# Robot2.net
KiCad netlist of a schematic drawn in EAGLE
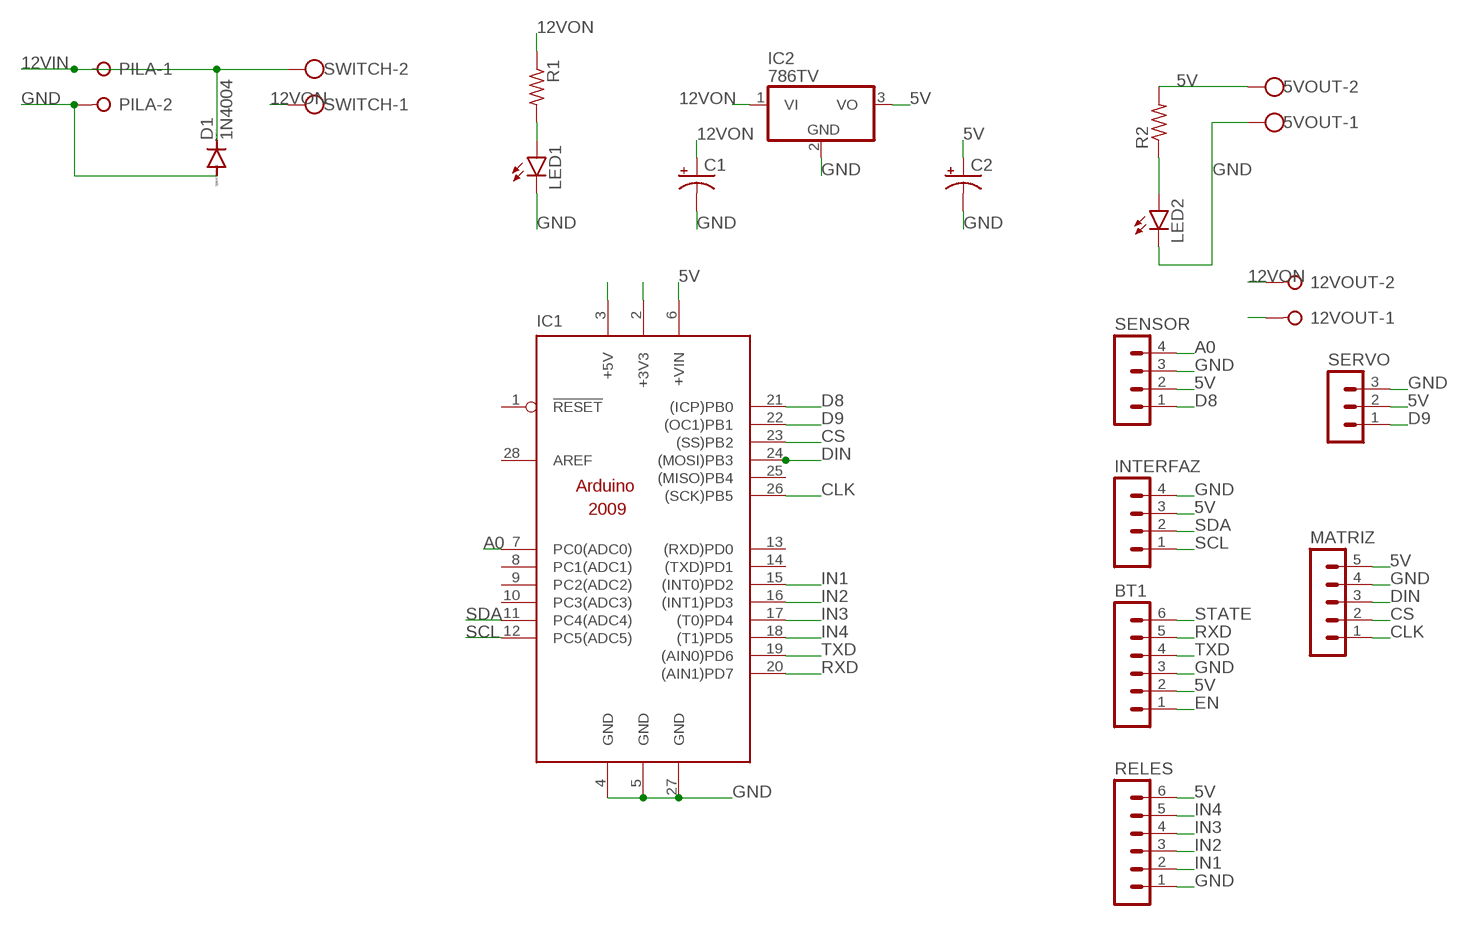
[diagram p0: schematic, sheet 1]

(export (version "E")
  (design (tool "Eeschema 10.0.6"))
  (components
    (comp (ref "5VOUT")
      (value "W237-102")
      (footprint "eagle-import:W237-102")
      (fields (field (name "MPN") "237-102"))
      (libsource (lib "eagle-import") (part "W237-102"))
    )
    (comp (ref "12VOUT")
      (value "W237-02P")
      (footprint "eagle-import:W237-132")
      (libsource (lib "eagle-import") (part "W237-02P"))
    )
    (comp (ref "BT1")
      (value "MA06-1")
      (footprint "eagle-import:MA06-1")
      (libsource (lib "eagle-import") (part "MA06-1"))
    )
    (comp (ref "C1")
      (value "CPOL-USE2,5-6E")
      (footprint "eagle-import:E2,5-6E")
      (libsource (lib "eagle-import") (part "CPOL-USE2,5-6E"))
    )
    (comp (ref "C2")
      (value "CPOL-USE2,5-6E")
      (footprint "eagle-import:E2,5-6E")
      (libsource (lib "eagle-import") (part "CPOL-USE2,5-6E"))
    )
    (comp (ref "D1")
      (value "1N4004")
      (footprint "eagle-import:DO41-10")
      (libsource (lib "eagle-import") (part "1N4004"))
    )
    (comp (ref "IC1")
      (value "ARDUINO2009_PIN_11")
      (footprint "eagle-import:ARDUINO2009_1")
      (libsource (lib "eagle-import") (part "ARDUINO2009_PIN_11"))
    )
    (comp (ref "IC2")
      (value "786TV")
      (footprint "eagle-import:TO220V")
      (libsource (lib "eagle-import") (part "78TV6"))
    )
    (comp (ref "INTERFAZ")
      (value "MA04-1")
      (footprint "eagle-import:MA04-1")
      (libsource (lib "eagle-import") (part "MA04-1"))
    )
    (comp (ref "LED1")
      (value "LED3MM")
      (footprint "eagle-import:LED3MM")
      (libsource (lib "eagle-import") (part "LED3MM"))
    )
    (comp (ref "LED2")
      (value "LED3MM")
      (footprint "eagle-import:LED3MM")
      (libsource (lib "eagle-import") (part "LED3MM"))
    )
    (comp (ref "MATRIZ")
      (value "MA05-1")
      (footprint "eagle-import:MA05-1")
      (libsource (lib "eagle-import") (part "MA05-1"))
    )
    (comp (ref "PILA")
      (value "W237-02P")
      (footprint "eagle-import:W237-132")
      (libsource (lib "eagle-import") (part "W237-02P"))
    )
    (comp (ref "R1")
      (value "R-US_0204/7")
      (footprint "eagle-import:0204_7")
      (libsource (lib "eagle-import") (part "R-US_0204/7"))
    )
    (comp (ref "R2")
      (value "R-US_0204/7")
      (footprint "eagle-import:0204_7")
      (libsource (lib "eagle-import") (part "R-US_0204/7"))
    )
    (comp (ref "RELES")
      (value "MA06-1")
      (footprint "eagle-import:MA06-1")
      (libsource (lib "eagle-import") (part "MA06-1"))
    )
    (comp (ref "SENSOR")
      (value "MA04-1")
      (footprint "eagle-import:MA04-1")
      (libsource (lib "eagle-import") (part "MA04-1"))
    )
    (comp (ref "SERVO")
      (value "MA03-1")
      (footprint "eagle-import:MA03-1")
      (libsource (lib "eagle-import") (part "MA03-1"))
    )
    (comp (ref "SWITCH")
      (value "W237-102")
      (footprint "eagle-import:W237-102")
      (fields (field (name "MPN") "237-102"))
      (libsource (lib "eagle-import") (part "W237-102"))
    )
  )
  (nets
    (net (code "1") (name "/5V") (class "Default")
      (node (ref "5VOUT") (pin "2") (pinfunction "KL_2") (pintype "passive"))
      (node (ref "BT1") (pin "2") (pinfunction "2_2") (pintype "passive"))
      (node (ref "C2") (pin "+") (pinfunction "+_+") (pintype "passive"))
      (node (ref "IC1") (pin "6") (pinfunction "+VIN_6") (pintype "bidirectional"))
      (node (ref "IC2") (pin "3") (pinfunction "VO_3") (pintype "passive"))
      (node (ref "INTERFAZ") (pin "3") (pinfunction "3_3") (pintype "passive"))
      (node (ref "MATRIZ") (pin "5") (pinfunction "5_5") (pintype "passive"))
      (node (ref "R2") (pin "2") (pinfunction "2_2") (pintype "passive"))
      (node (ref "RELES") (pin "6") (pinfunction "6_6") (pintype "passive"))
      (node (ref "SENSOR") (pin "2") (pinfunction "2_2") (pintype "passive"))
      (node (ref "SERVO") (pin "2") (pinfunction "2_2") (pintype "passive"))
    )
    (net (code "2") (name "/12VIN") (class "Default")
      (node (ref "D1") (pin "C") (pinfunction "C_C") (pintype "passive"))
      (node (ref "PILA") (pin "1") (pinfunction "KL_1") (pintype "passive"))
      (node (ref "SWITCH") (pin "2") (pinfunction "KL_2") (pintype "passive"))
    )
    (net (code "3") (name "/12VON") (class "Default")
      (node (ref "12VOUT") (pin "2") (pinfunction "KL_2") (pintype "passive"))
      (node (ref "C1") (pin "+") (pinfunction "+_+") (pintype "passive"))
      (node (ref "IC2") (pin "1") (pinfunction "VI_1") (pintype "input"))
      (node (ref "R1") (pin "1") (pinfunction "1_1") (pintype "passive"))
      (node (ref "SWITCH") (pin "1") (pinfunction "KL_1") (pintype "passive"))
    )
    (net (code "4") (name "/A0") (class "Default")
      (node (ref "IC1") (pin "7") (pinfunction "PC0(ADC0)_7") (pintype "bidirectional"))
      (node (ref "SENSOR") (pin "4") (pinfunction "4_4") (pintype "passive"))
    )
    (net (code "5") (name "/CLK") (class "Default")
      (node (ref "IC1") (pin "26") (pinfunction "(SCK)PB5_26") (pintype "bidirectional"))
      (node (ref "MATRIZ") (pin "1") (pinfunction "1_1") (pintype "passive"))
    )
    (net (code "6") (name "/CS") (class "Default")
      (node (ref "IC1") (pin "23") (pinfunction "(SS)PB2_23") (pintype "bidirectional"))
      (node (ref "MATRIZ") (pin "2") (pinfunction "2_2") (pintype "passive"))
    )
    (net (code "7") (name "/D8") (class "Default")
      (node (ref "IC1") (pin "21") (pinfunction "(ICP)PB0_21") (pintype "bidirectional"))
      (node (ref "SENSOR") (pin "1") (pinfunction "1_1") (pintype "passive"))
    )
    (net (code "8") (name "/D9") (class "Default")
      (node (ref "IC1") (pin "22") (pinfunction "(OC1)PB1_22") (pintype "bidirectional"))
      (node (ref "SERVO") (pin "1") (pinfunction "1_1") (pintype "passive"))
    )
    (net (code "9") (name "/DIN") (class "Default")
      (node (ref "IC1") (pin "24") (pinfunction "(MOSI)PB3_24") (pintype "bidirectional"))
      (node (ref "MATRIZ") (pin "3") (pinfunction "3_3") (pintype "passive"))
    )
    (net (code "10") (name "/EN") (class "Default")
      (node (ref "BT1") (pin "1") (pinfunction "1_1") (pintype "passive"))
    )
    (net (code "11") (name "/GND") (class "Default")
      (node (ref "12VOUT") (pin "1") (pinfunction "KL_1") (pintype "passive"))
      (node (ref "5VOUT") (pin "1") (pinfunction "KL_1") (pintype "passive"))
      (node (ref "BT1") (pin "3") (pinfunction "3_3") (pintype "passive"))
      (node (ref "C1") (pin "-") (pinfunction "-_-") (pintype "passive"))
      (node (ref "C2") (pin "-") (pinfunction "-_-") (pintype "passive"))
      (node (ref "D1") (pin "A") (pinfunction "A_A") (pintype "passive"))
      (node (ref "IC1") (pin "27") (pinfunction "GND_27") (pintype "power_in"))
      (node (ref "IC1") (pin "4") (pinfunction "GND_4") (pintype "power_in"))
      (node (ref "IC1") (pin "5") (pinfunction "GND_5") (pintype "power_in"))
      (node (ref "IC2") (pin "2") (pinfunction "GND_2") (pintype "passive"))
      (node (ref "INTERFAZ") (pin "4") (pinfunction "4_4") (pintype "passive"))
      (node (ref "LED1") (pin "K") (pinfunction "C_K") (pintype "passive"))
      (node (ref "LED2") (pin "K") (pinfunction "C_K") (pintype "passive"))
      (node (ref "MATRIZ") (pin "4") (pinfunction "4_4") (pintype "passive"))
      (node (ref "PILA") (pin "2") (pinfunction "KL_2") (pintype "passive"))
      (node (ref "RELES") (pin "1") (pinfunction "1_1") (pintype "passive"))
      (node (ref "SENSOR") (pin "3") (pinfunction "3_3") (pintype "passive"))
      (node (ref "SERVO") (pin "3") (pinfunction "3_3") (pintype "passive"))
    )
    (net (code "12") (name "/IN1") (class "Default")
      (node (ref "IC1") (pin "15") (pinfunction "(INT0)PD2_15") (pintype "bidirectional"))
      (node (ref "RELES") (pin "2") (pinfunction "2_2") (pintype "passive"))
    )
    (net (code "13") (name "/IN2") (class "Default")
      (node (ref "IC1") (pin "16") (pinfunction "(INT1)PD3_16") (pintype "bidirectional"))
      (node (ref "RELES") (pin "3") (pinfunction "3_3") (pintype "passive"))
    )
    (net (code "14") (name "/IN3") (class "Default")
      (node (ref "IC1") (pin "17") (pinfunction "(T0)PD4_17") (pintype "bidirectional"))
      (node (ref "RELES") (pin "4") (pinfunction "4_4") (pintype "passive"))
    )
    (net (code "15") (name "/IN4") (class "Default")
      (node (ref "IC1") (pin "18") (pinfunction "(T1)PD5_18") (pintype "bidirectional"))
      (node (ref "RELES") (pin "5") (pinfunction "5_5") (pintype "passive"))
    )
    (net (code "16") (name "/RXD") (class "Default")
      (node (ref "BT1") (pin "5") (pinfunction "5_5") (pintype "passive"))
      (node (ref "IC1") (pin "20") (pinfunction "(AIN1)PD7_20") (pintype "bidirectional"))
    )
    (net (code "17") (name "/SCL") (class "Default")
      (node (ref "IC1") (pin "12") (pinfunction "PC5(ADC5)_12") (pintype "bidirectional"))
      (node (ref "INTERFAZ") (pin "1") (pinfunction "1_1") (pintype "passive"))
    )
    (net (code "18") (name "/SDA") (class "Default")
      (node (ref "IC1") (pin "11") (pinfunction "PC4(ADC4)_11") (pintype "bidirectional"))
      (node (ref "INTERFAZ") (pin "2") (pinfunction "2_2") (pintype "passive"))
    )
    (net (code "19") (name "/STATE") (class "Default")
      (node (ref "BT1") (pin "6") (pinfunction "6_6") (pintype "passive"))
    )
    (net (code "20") (name "/TXD") (class "Default")
      (node (ref "BT1") (pin "4") (pinfunction "4_4") (pintype "passive"))
      (node (ref "IC1") (pin "19") (pinfunction "(AIN0)PD6_19") (pintype "bidirectional"))
    )
    (net (code "21") (name "Net-(LED1-PadA)") (class "Default")
      (node (ref "LED1") (pin "A") (pinfunction "A_A") (pintype "passive"))
      (node (ref "R1") (pin "2") (pinfunction "2_2") (pintype "passive"))
    )
    (net (code "22") (name "Net-(LED2-PadA)") (class "Default")
      (node (ref "LED2") (pin "A") (pinfunction "A_A") (pintype "passive"))
      (node (ref "R2") (pin "1") (pinfunction "1_1") (pintype "passive"))
    )
    (net (code "23") (name "unconnected-(IC1-(MISO)PB4-Pad25)") (class "Default")
      (node (ref "IC1") (pin "25") (pinfunction "(MISO)PB4_25") (pintype "bidirectional"))
    )
    (net (code "24") (name "unconnected-(IC1-(RXD)PD0-Pad13)") (class "Default")
      (node (ref "IC1") (pin "13") (pinfunction "(RXD)PD0_13") (pintype "bidirectional"))
    )
    (net (code "25") (name "unconnected-(IC1-(TXD)PD1-Pad14)") (class "Default")
      (node (ref "IC1") (pin "14") (pinfunction "(TXD)PD1_14") (pintype "bidirectional"))
    )
    (net (code "26") (name "unconnected-(IC1-+3V3-Pad2)") (class "Default")
      (node (ref "IC1") (pin "2") (pinfunction "+3V3_2") (pintype "power_in"))
    )
    (net (code "27") (name "unconnected-(IC1-+5V-Pad3)") (class "Default")
      (node (ref "IC1") (pin "3") (pinfunction "+5V_3") (pintype "power_in"))
    )
    (net (code "28") (name "unconnected-(IC1-AREF-Pad28)") (class "Default")
      (node (ref "IC1") (pin "28") (pinfunction "AREF_28") (pintype "bidirectional"))
    )
    (net (code "29") (name "unconnected-(IC1-PC1(ADC1)-Pad8)") (class "Default")
      (node (ref "IC1") (pin "8") (pinfunction "PC1(ADC1)_8") (pintype "bidirectional"))
    )
    (net (code "30") (name "unconnected-(IC1-PC2(ADC2)-Pad9)") (class "Default")
      (node (ref "IC1") (pin "9") (pinfunction "PC2(ADC2)_9") (pintype "bidirectional"))
    )
    (net (code "31") (name "unconnected-(IC1-PC3(ADC3)-Pad10)") (class "Default")
      (node (ref "IC1") (pin "10") (pinfunction "PC3(ADC3)_10") (pintype "bidirectional"))
    )
    (net (code "32") (name "unconnected-(IC1-~{RESET}-Pad1)") (class "Default")
      (node (ref "IC1") (pin "1") (pinfunction "~{RESET}_1") (pintype "bidirectional"))
    )
  )
)
